# breakout.net
KiCad netlist of a schematic drawn in EAGLE
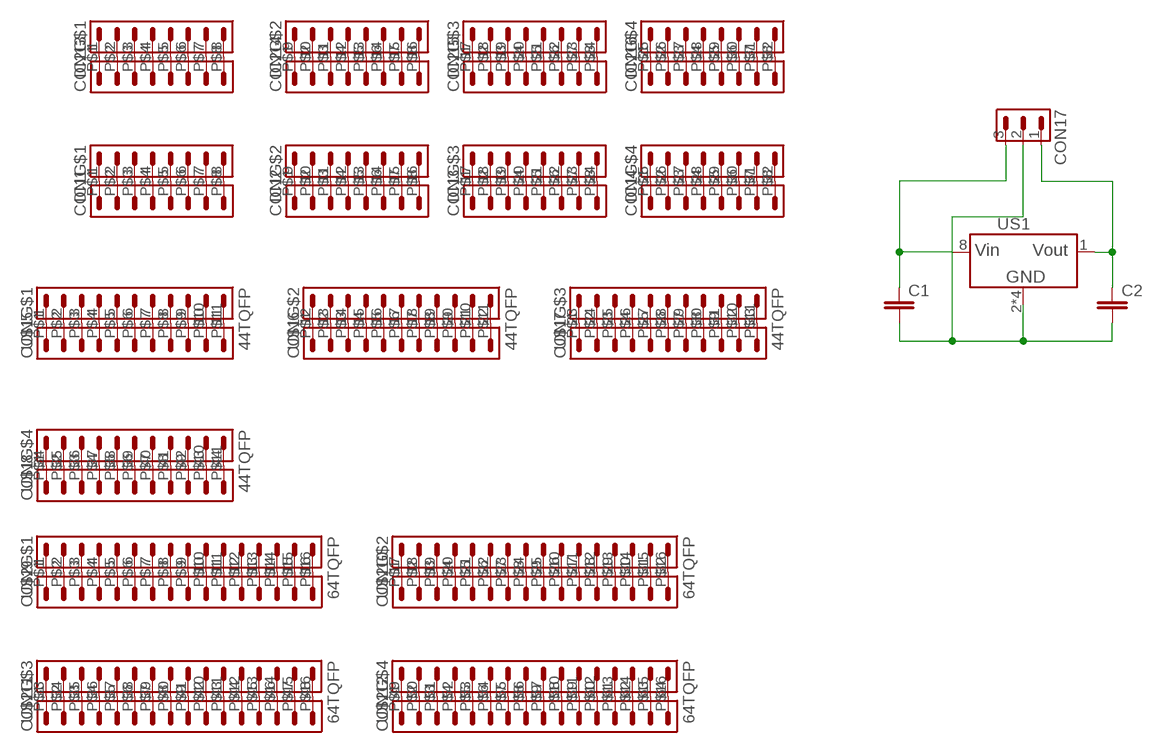
[diagram p0: schematic, sheet 1]

(export (version "E")
  (design (tool "Eeschema 10.0.6"))
  (components
    (comp (ref "C1")
      (value "C0603")
      (footprint "eagle-import:0603")
      (libsource (lib "eagle-import") (part "C0603"))
    )
    (comp (ref "C2")
      (value "C0603")
      (footprint "eagle-import:0603")
      (libsource (lib "eagle-import") (part "C0603"))
    )
    (comp (ref "CON1")
      (value "PIN8X1_SM50")
      (footprint "eagle-import:PIN8X1_SM50")
      (libsource (lib "eagle-import") (part "PIN8X1_SM50"))
    )
    (comp (ref "CON2")
      (value "PIN8X1_SM50")
      (footprint "eagle-import:PIN8X1_SM50")
      (libsource (lib "eagle-import") (part "PIN8X1_SM50"))
    )
    (comp (ref "CON3")
      (value "PIN8X1_SM50")
      (footprint "eagle-import:PIN8X1_SM50")
      (libsource (lib "eagle-import") (part "PIN8X1_SM50"))
    )
    (comp (ref "CON4")
      (value "PIN8X1_SM50")
      (footprint "eagle-import:PIN8X1_SM50")
      (libsource (lib "eagle-import") (part "PIN8X1_SM50"))
    )
    (comp (ref "CON5")
      (value "PIN11X1_SM50")
      (footprint "eagle-import:PIN11X1_SM50")
      (libsource (lib "eagle-import") (part "PIN11X1_SM50"))
    )
    (comp (ref "CON6")
      (value "PIN11X1_SM50")
      (footprint "eagle-import:PIN11X1_SM50")
      (libsource (lib "eagle-import") (part "PIN11X1_SM50"))
    )
    (comp (ref "CON7")
      (value "PIN11X1_SM50")
      (footprint "eagle-import:PIN11X1_SM50")
      (libsource (lib "eagle-import") (part "PIN11X1_SM50"))
    )
    (comp (ref "CON8")
      (value "PIN11X1_SM50")
      (footprint "eagle-import:PIN11X1_SM50")
      (libsource (lib "eagle-import") (part "PIN11X1_SM50"))
    )
    (comp (ref "CON9")
      (value "PIN16X1_SM50")
      (footprint "eagle-import:PIN16X1_SM50")
      (libsource (lib "eagle-import") (part "PIN16X1_SM50"))
    )
    (comp (ref "CON10")
      (value "PIN16X1_SM50")
      (footprint "eagle-import:PIN16X1_SM50")
      (libsource (lib "eagle-import") (part "PIN16X1_SM50"))
    )
    (comp (ref "CON11")
      (value "PIN16X1_SM50")
      (footprint "eagle-import:PIN16X1_SM50")
      (libsource (lib "eagle-import") (part "PIN16X1_SM50"))
    )
    (comp (ref "CON12")
      (value "PIN16X1_SM50")
      (footprint "eagle-import:PIN16X1_SM50")
      (libsource (lib "eagle-import") (part "PIN16X1_SM50"))
    )
    (comp (ref "CON13")
      (value "PIN8X1_SM50")
      (footprint "eagle-import:PIN8X1_SM50")
      (libsource (lib "eagle-import") (part "PIN8X1_SM50"))
    )
    (comp (ref "CON14")
      (value "PIN8X1_SM50")
      (footprint "eagle-import:PIN8X1_SM50")
      (libsource (lib "eagle-import") (part "PIN8X1_SM50"))
    )
    (comp (ref "CON15")
      (value "PIN8X1_SM50")
      (footprint "eagle-import:PIN8X1_SM50")
      (libsource (lib "eagle-import") (part "PIN8X1_SM50"))
    )
    (comp (ref "CON16")
      (value "PIN8X1_SM50")
      (footprint "eagle-import:PIN8X1_SM50")
      (libsource (lib "eagle-import") (part "PIN8X1_SM50"))
    )
    (comp (ref "CON17")
      (value "PIN3X1")
      (footprint "eagle-import:PIN3X1")
      (libsource (lib "eagle-import") (part "PIN3X1"))
    )
    (comp (ref "IC1")
      (value "32TQFP")
      (footprint "eagle-import:TQFP32")
      (libsource (lib "eagle-import") (part "32TQFP"))
    )
    (comp (ref "IC2")
      (value "32MLF")
      (footprint "eagle-import:MLF32-TH")
      (libsource (lib "eagle-import") (part "32MLF"))
    )
    (comp (ref "U$1")
      (value "44TQFP")
      (footprint "eagle-import:TQFP44")
      (libsource (lib "eagle-import") (part "44TQFP"))
    )
    (comp (ref "U$2")
      (value "64TQFP")
      (footprint "eagle-import:TQFP64")
      (libsource (lib "eagle-import") (part "64TQFP"))
    )
    (comp (ref "US1")
      (value "VREG+L-SO8")
      (footprint "eagle-import:SO08")
      (libsource (lib "eagle-import") (part "VREG+L-SO8"))
    )
  )
  (nets
    (net (code "1") (name "Net-(C1-Pad2)") (class "Default")
      (node (ref "C1") (pin "2") (pinfunction "2_2") (pintype "passive"))
      (node (ref "C2") (pin "2") (pinfunction "2_2") (pintype "passive"))
      (node (ref "CON17") (pin "2") (pinfunction "2_2") (pintype "passive"))
      (node (ref "US1") (pin "2") (pinfunction "GND_2") (pintype "passive"))
      (node (ref "US1") (pin "3") (pinfunction "GND_3") (pintype "passive"))
      (node (ref "US1") (pin "6") (pinfunction "GND_6") (pintype "passive"))
      (node (ref "US1") (pin "7") (pinfunction "GND_7") (pintype "passive"))
    )
    (net (code "2") (name "Net-(CON1-1)") (class "Default")
      (node (ref "CON1") (pin "P$1") (pinfunction "1_P$1") (pintype "passive"))
      (node (ref "IC1") (pin "1") (pinfunction "1_1") (pintype "passive"))
    )
    (net (code "3") (name "Net-(CON1-2)") (class "Default")
      (node (ref "CON1") (pin "P$2") (pinfunction "2_P$2") (pintype "passive"))
      (node (ref "IC1") (pin "2") (pinfunction "2_2") (pintype "passive"))
    )
    (net (code "4") (name "Net-(CON1-3)") (class "Default")
      (node (ref "CON1") (pin "P$3") (pinfunction "3_P$3") (pintype "passive"))
      (node (ref "IC1") (pin "3") (pinfunction "3_3") (pintype "passive"))
    )
    (net (code "5") (name "Net-(CON1-4)") (class "Default")
      (node (ref "CON1") (pin "P$4") (pinfunction "4_P$4") (pintype "passive"))
      (node (ref "IC1") (pin "4") (pinfunction "4_4") (pintype "passive"))
    )
    (net (code "6") (name "Net-(CON1-5)") (class "Default")
      (node (ref "CON1") (pin "P$5") (pinfunction "5_P$5") (pintype "passive"))
      (node (ref "IC1") (pin "5") (pinfunction "5_5") (pintype "passive"))
    )
    (net (code "7") (name "Net-(CON1-6)") (class "Default")
      (node (ref "CON1") (pin "P$6") (pinfunction "6_P$6") (pintype "passive"))
      (node (ref "IC1") (pin "6") (pinfunction "6_6") (pintype "passive"))
    )
    (net (code "8") (name "Net-(CON1-7)") (class "Default")
      (node (ref "CON1") (pin "P$7") (pinfunction "7_P$7") (pintype "passive"))
      (node (ref "IC1") (pin "7") (pinfunction "7_7") (pintype "passive"))
    )
    (net (code "9") (name "Net-(CON1-8)") (class "Default")
      (node (ref "CON1") (pin "P$8") (pinfunction "8_P$8") (pintype "passive"))
      (node (ref "IC1") (pin "8") (pinfunction "8_8") (pintype "passive"))
    )
    (net (code "10") (name "Net-(CON2-1)") (class "Default")
      (node (ref "CON2") (pin "P$1") (pinfunction "1_P$1") (pintype "passive"))
      (node (ref "IC1") (pin "9") (pinfunction "1_9") (pintype "passive"))
    )
    (net (code "11") (name "Net-(CON2-2)") (class "Default")
      (node (ref "CON2") (pin "P$2") (pinfunction "2_P$2") (pintype "passive"))
      (node (ref "IC1") (pin "10") (pinfunction "2_10") (pintype "passive"))
    )
    (net (code "12") (name "Net-(CON2-3)") (class "Default")
      (node (ref "CON2") (pin "P$3") (pinfunction "3_P$3") (pintype "passive"))
      (node (ref "IC1") (pin "11") (pinfunction "3_11") (pintype "passive"))
    )
    (net (code "13") (name "Net-(CON2-4)") (class "Default")
      (node (ref "CON2") (pin "P$4") (pinfunction "4_P$4") (pintype "passive"))
      (node (ref "IC1") (pin "12") (pinfunction "4_12") (pintype "passive"))
    )
    (net (code "14") (name "Net-(CON2-5)") (class "Default")
      (node (ref "CON2") (pin "P$5") (pinfunction "5_P$5") (pintype "passive"))
      (node (ref "IC1") (pin "13") (pinfunction "5_13") (pintype "passive"))
    )
    (net (code "15") (name "Net-(CON2-6)") (class "Default")
      (node (ref "CON2") (pin "P$6") (pinfunction "6_P$6") (pintype "passive"))
      (node (ref "IC1") (pin "14") (pinfunction "6_14") (pintype "passive"))
    )
    (net (code "16") (name "Net-(CON2-7)") (class "Default")
      (node (ref "CON2") (pin "P$7") (pinfunction "7_P$7") (pintype "passive"))
      (node (ref "IC1") (pin "15") (pinfunction "7_15") (pintype "passive"))
    )
    (net (code "17") (name "Net-(CON2-8)") (class "Default")
      (node (ref "CON2") (pin "P$8") (pinfunction "8_P$8") (pintype "passive"))
      (node (ref "IC1") (pin "16") (pinfunction "8_16") (pintype "passive"))
    )
    (net (code "18") (name "Net-(CON3-1)") (class "Default")
      (node (ref "CON3") (pin "P$1") (pinfunction "1_P$1") (pintype "passive"))
      (node (ref "IC1") (pin "17") (pinfunction "1_17") (pintype "passive"))
    )
    (net (code "19") (name "Net-(CON3-2)") (class "Default")
      (node (ref "CON3") (pin "P$2") (pinfunction "2_P$2") (pintype "passive"))
      (node (ref "IC1") (pin "18") (pinfunction "2_18") (pintype "passive"))
    )
    (net (code "20") (name "Net-(CON3-3)") (class "Default")
      (node (ref "CON3") (pin "P$3") (pinfunction "3_P$3") (pintype "passive"))
      (node (ref "IC1") (pin "19") (pinfunction "3_19") (pintype "passive"))
    )
    (net (code "21") (name "Net-(CON3-4)") (class "Default")
      (node (ref "CON3") (pin "P$4") (pinfunction "4_P$4") (pintype "passive"))
      (node (ref "IC1") (pin "20") (pinfunction "4_20") (pintype "passive"))
    )
    (net (code "22") (name "Net-(CON3-5)") (class "Default")
      (node (ref "CON3") (pin "P$5") (pinfunction "5_P$5") (pintype "passive"))
      (node (ref "IC1") (pin "21") (pinfunction "5_21") (pintype "passive"))
    )
    (net (code "23") (name "Net-(CON3-6)") (class "Default")
      (node (ref "CON3") (pin "P$6") (pinfunction "6_P$6") (pintype "passive"))
      (node (ref "IC1") (pin "22") (pinfunction "6_22") (pintype "passive"))
    )
    (net (code "24") (name "Net-(CON3-7)") (class "Default")
      (node (ref "CON3") (pin "P$7") (pinfunction "7_P$7") (pintype "passive"))
      (node (ref "IC1") (pin "23") (pinfunction "7_23") (pintype "passive"))
    )
    (net (code "25") (name "Net-(CON3-8)") (class "Default")
      (node (ref "CON3") (pin "P$8") (pinfunction "8_P$8") (pintype "passive"))
      (node (ref "IC1") (pin "24") (pinfunction "8_24") (pintype "passive"))
    )
    (net (code "26") (name "Net-(CON4-1)") (class "Default")
      (node (ref "CON4") (pin "P$1") (pinfunction "1_P$1") (pintype "passive"))
      (node (ref "IC1") (pin "25") (pinfunction "1_25") (pintype "passive"))
    )
    (net (code "27") (name "Net-(CON4-2)") (class "Default")
      (node (ref "CON4") (pin "P$2") (pinfunction "2_P$2") (pintype "passive"))
      (node (ref "IC1") (pin "26") (pinfunction "2_26") (pintype "passive"))
    )
    (net (code "28") (name "Net-(CON4-3)") (class "Default")
      (node (ref "CON4") (pin "P$3") (pinfunction "3_P$3") (pintype "passive"))
      (node (ref "IC1") (pin "27") (pinfunction "3_27") (pintype "passive"))
    )
    (net (code "29") (name "Net-(CON4-4)") (class "Default")
      (node (ref "CON4") (pin "P$4") (pinfunction "4_P$4") (pintype "passive"))
      (node (ref "IC1") (pin "28") (pinfunction "4_28") (pintype "passive"))
    )
    (net (code "30") (name "Net-(CON4-5)") (class "Default")
      (node (ref "CON4") (pin "P$5") (pinfunction "5_P$5") (pintype "passive"))
      (node (ref "IC1") (pin "29") (pinfunction "5_29") (pintype "passive"))
    )
    (net (code "31") (name "Net-(CON4-6)") (class "Default")
      (node (ref "CON4") (pin "P$6") (pinfunction "6_P$6") (pintype "passive"))
      (node (ref "IC1") (pin "30") (pinfunction "6_30") (pintype "passive"))
    )
    (net (code "32") (name "Net-(CON4-7)") (class "Default")
      (node (ref "CON4") (pin "P$7") (pinfunction "7_P$7") (pintype "passive"))
      (node (ref "IC1") (pin "31") (pinfunction "7_31") (pintype "passive"))
    )
    (net (code "33") (name "Net-(CON4-8)") (class "Default")
      (node (ref "CON4") (pin "P$8") (pinfunction "8_P$8") (pintype "passive"))
      (node (ref "IC1") (pin "32") (pinfunction "8_32") (pintype "passive"))
    )
    (net (code "34") (name "Net-(CON5-1)") (class "Default")
      (node (ref "CON5") (pin "P$1") (pinfunction "1_P$1") (pintype "passive"))
      (node (ref "U$1") (pin "1") (pinfunction "1_1") (pintype "passive"))
    )
    (net (code "35") (name "Net-(CON5-2)") (class "Default")
      (node (ref "CON5") (pin "P$2") (pinfunction "2_P$2") (pintype "passive"))
      (node (ref "U$1") (pin "2") (pinfunction "2_2") (pintype "passive"))
    )
    (net (code "36") (name "Net-(CON5-3)") (class "Default")
      (node (ref "CON5") (pin "P$3") (pinfunction "3_P$3") (pintype "passive"))
      (node (ref "U$1") (pin "3") (pinfunction "3_3") (pintype "passive"))
    )
    (net (code "37") (name "Net-(CON5-4)") (class "Default")
      (node (ref "CON5") (pin "P$4") (pinfunction "4_P$4") (pintype "passive"))
      (node (ref "U$1") (pin "4") (pinfunction "4_4") (pintype "passive"))
    )
    (net (code "38") (name "Net-(CON5-5)") (class "Default")
      (node (ref "CON5") (pin "P$5") (pinfunction "5_P$5") (pintype "passive"))
      (node (ref "U$1") (pin "5") (pinfunction "5_5") (pintype "passive"))
    )
    (net (code "39") (name "Net-(CON5-6)") (class "Default")
      (node (ref "CON5") (pin "P$6") (pinfunction "6_P$6") (pintype "passive"))
      (node (ref "U$1") (pin "6") (pinfunction "6_6") (pintype "passive"))
    )
    (net (code "40") (name "Net-(CON5-7)") (class "Default")
      (node (ref "CON5") (pin "P$7") (pinfunction "7_P$7") (pintype "passive"))
      (node (ref "U$1") (pin "7") (pinfunction "7_7") (pintype "passive"))
    )
    (net (code "41") (name "Net-(CON5-8)") (class "Default")
      (node (ref "CON5") (pin "P$8") (pinfunction "8_P$8") (pintype "passive"))
      (node (ref "U$1") (pin "8") (pinfunction "8_8") (pintype "passive"))
    )
    (net (code "42") (name "Net-(CON5-9)") (class "Default")
      (node (ref "CON5") (pin "P$9") (pinfunction "9_P$9") (pintype "passive"))
      (node (ref "U$1") (pin "9") (pinfunction "9_9") (pintype "passive"))
    )
    (net (code "43") (name "Net-(CON5-10)") (class "Default")
      (node (ref "CON5") (pin "P$10") (pinfunction "10_P$10") (pintype "passive"))
      (node (ref "U$1") (pin "10") (pinfunction "10_10") (pintype "passive"))
    )
    (net (code "44") (name "Net-(CON5-11)") (class "Default")
      (node (ref "CON5") (pin "P$11") (pinfunction "11_P$11") (pintype "passive"))
      (node (ref "U$1") (pin "11") (pinfunction "11_11") (pintype "passive"))
    )
    (net (code "45") (name "Net-(CON6-1)") (class "Default")
      (node (ref "CON6") (pin "P$1") (pinfunction "1_P$1") (pintype "passive"))
      (node (ref "U$1") (pin "12") (pinfunction "1_12") (pintype "passive"))
    )
    (net (code "46") (name "Net-(CON6-2)") (class "Default")
      (node (ref "CON6") (pin "P$2") (pinfunction "2_P$2") (pintype "passive"))
      (node (ref "U$1") (pin "13") (pinfunction "2_13") (pintype "passive"))
    )
    (net (code "47") (name "Net-(CON6-3)") (class "Default")
      (node (ref "CON6") (pin "P$3") (pinfunction "3_P$3") (pintype "passive"))
      (node (ref "U$1") (pin "14") (pinfunction "3_14") (pintype "passive"))
    )
    (net (code "48") (name "Net-(CON6-4)") (class "Default")
      (node (ref "CON6") (pin "P$4") (pinfunction "4_P$4") (pintype "passive"))
      (node (ref "U$1") (pin "15") (pinfunction "4_15") (pintype "passive"))
    )
    (net (code "49") (name "Net-(CON6-5)") (class "Default")
      (node (ref "CON6") (pin "P$5") (pinfunction "5_P$5") (pintype "passive"))
      (node (ref "U$1") (pin "16") (pinfunction "5_16") (pintype "passive"))
    )
    (net (code "50") (name "Net-(CON6-6)") (class "Default")
      (node (ref "CON6") (pin "P$6") (pinfunction "6_P$6") (pintype "passive"))
      (node (ref "U$1") (pin "17") (pinfunction "6_17") (pintype "passive"))
    )
    (net (code "51") (name "Net-(CON6-7)") (class "Default")
      (node (ref "CON6") (pin "P$7") (pinfunction "7_P$7") (pintype "passive"))
      (node (ref "U$1") (pin "18") (pinfunction "7_18") (pintype "passive"))
    )
    (net (code "52") (name "Net-(CON6-8)") (class "Default")
      (node (ref "CON6") (pin "P$8") (pinfunction "8_P$8") (pintype "passive"))
      (node (ref "U$1") (pin "19") (pinfunction "8_19") (pintype "passive"))
    )
    (net (code "53") (name "Net-(CON6-9)") (class "Default")
      (node (ref "CON6") (pin "P$9") (pinfunction "9_P$9") (pintype "passive"))
      (node (ref "U$1") (pin "20") (pinfunction "9_20") (pintype "passive"))
    )
    (net (code "54") (name "Net-(CON6-10)") (class "Default")
      (node (ref "CON6") (pin "P$10") (pinfunction "10_P$10") (pintype "passive"))
      (node (ref "U$1") (pin "21") (pinfunction "10_21") (pintype "passive"))
    )
    (net (code "55") (name "Net-(CON6-11)") (class "Default")
      (node (ref "CON6") (pin "P$11") (pinfunction "11_P$11") (pintype "passive"))
      (node (ref "U$1") (pin "22") (pinfunction "11_22") (pintype "passive"))
    )
    (net (code "56") (name "Net-(CON7-1)") (class "Default")
      (node (ref "CON7") (pin "P$1") (pinfunction "1_P$1") (pintype "passive"))
      (node (ref "U$1") (pin "23") (pinfunction "1_23") (pintype "passive"))
    )
    (net (code "57") (name "Net-(CON7-2)") (class "Default")
      (node (ref "CON7") (pin "P$2") (pinfunction "2_P$2") (pintype "passive"))
      (node (ref "U$1") (pin "24") (pinfunction "2_24") (pintype "passive"))
    )
    (net (code "58") (name "Net-(CON7-3)") (class "Default")
      (node (ref "CON7") (pin "P$3") (pinfunction "3_P$3") (pintype "passive"))
      (node (ref "U$1") (pin "25") (pinfunction "3_25") (pintype "passive"))
    )
    (net (code "59") (name "Net-(CON7-4)") (class "Default")
      (node (ref "CON7") (pin "P$4") (pinfunction "4_P$4") (pintype "passive"))
      (node (ref "U$1") (pin "26") (pinfunction "4_26") (pintype "passive"))
    )
    (net (code "60") (name "Net-(CON7-5)") (class "Default")
      (node (ref "CON7") (pin "P$5") (pinfunction "5_P$5") (pintype "passive"))
      (node (ref "U$1") (pin "27") (pinfunction "5_27") (pintype "passive"))
    )
    (net (code "61") (name "Net-(CON7-6)") (class "Default")
      (node (ref "CON7") (pin "P$6") (pinfunction "6_P$6") (pintype "passive"))
      (node (ref "U$1") (pin "28") (pinfunction "6_28") (pintype "passive"))
    )
    (net (code "62") (name "Net-(CON7-7)") (class "Default")
      (node (ref "CON7") (pin "P$7") (pinfunction "7_P$7") (pintype "passive"))
      (node (ref "U$1") (pin "29") (pinfunction "7_29") (pintype "passive"))
    )
    (net (code "63") (name "Net-(CON7-8)") (class "Default")
      (node (ref "CON7") (pin "P$8") (pinfunction "8_P$8") (pintype "passive"))
      (node (ref "U$1") (pin "30") (pinfunction "8_30") (pintype "passive"))
    )
    (net (code "64") (name "Net-(CON7-9)") (class "Default")
      (node (ref "CON7") (pin "P$9") (pinfunction "9_P$9") (pintype "passive"))
      (node (ref "U$1") (pin "31") (pinfunction "9_31") (pintype "passive"))
    )
    (net (code "65") (name "Net-(CON7-10)") (class "Default")
      (node (ref "CON7") (pin "P$10") (pinfunction "10_P$10") (pintype "passive"))
      (node (ref "U$1") (pin "32") (pinfunction "10_32") (pintype "passive"))
    )
    (net (code "66") (name "Net-(CON7-11)") (class "Default")
      (node (ref "CON7") (pin "P$11") (pinfunction "11_P$11") (pintype "passive"))
      (node (ref "U$1") (pin "33") (pinfunction "11_33") (pintype "passive"))
    )
    (net (code "67") (name "Net-(CON8-1)") (class "Default")
      (node (ref "CON8") (pin "P$1") (pinfunction "1_P$1") (pintype "passive"))
      (node (ref "U$1") (pin "34") (pinfunction "1_34") (pintype "passive"))
    )
    (net (code "68") (name "Net-(CON8-2)") (class "Default")
      (node (ref "CON8") (pin "P$2") (pinfunction "2_P$2") (pintype "passive"))
      (node (ref "U$1") (pin "35") (pinfunction "2_35") (pintype "passive"))
    )
    (net (code "69") (name "Net-(CON8-3)") (class "Default")
      (node (ref "CON8") (pin "P$3") (pinfunction "3_P$3") (pintype "passive"))
      (node (ref "U$1") (pin "36") (pinfunction "3_36") (pintype "passive"))
    )
    (net (code "70") (name "Net-(CON8-4)") (class "Default")
      (node (ref "CON8") (pin "P$4") (pinfunction "4_P$4") (pintype "passive"))
      (node (ref "U$1") (pin "37") (pinfunction "4_37") (pintype "passive"))
    )
    (net (code "71") (name "Net-(CON8-5)") (class "Default")
      (node (ref "CON8") (pin "P$5") (pinfunction "5_P$5") (pintype "passive"))
      (node (ref "U$1") (pin "38") (pinfunction "5_38") (pintype "passive"))
    )
    (net (code "72") (name "Net-(CON8-6)") (class "Default")
      (node (ref "CON8") (pin "P$6") (pinfunction "6_P$6") (pintype "passive"))
      (node (ref "U$1") (pin "39") (pinfunction "6_39") (pintype "passive"))
    )
    (net (code "73") (name "Net-(CON8-7)") (class "Default")
      (node (ref "CON8") (pin "P$7") (pinfunction "7_P$7") (pintype "passive"))
      (node (ref "U$1") (pin "40") (pinfunction "7_40") (pintype "passive"))
    )
    (net (code "74") (name "Net-(CON8-8)") (class "Default")
      (node (ref "CON8") (pin "P$8") (pinfunction "8_P$8") (pintype "passive"))
      (node (ref "U$1") (pin "41") (pinfunction "8_41") (pintype "passive"))
    )
    (net (code "75") (name "Net-(CON8-9)") (class "Default")
      (node (ref "CON8") (pin "P$9") (pinfunction "9_P$9") (pintype "passive"))
      (node (ref "U$1") (pin "42") (pinfunction "9_42") (pintype "passive"))
    )
    (net (code "76") (name "Net-(CON8-10)") (class "Default")
      (node (ref "CON8") (pin "P$10") (pinfunction "10_P$10") (pintype "passive"))
      (node (ref "U$1") (pin "43") (pinfunction "10_43") (pintype "passive"))
    )
    (net (code "77") (name "Net-(CON8-11)") (class "Default")
      (node (ref "CON8") (pin "P$11") (pinfunction "11_P$11") (pintype "passive"))
      (node (ref "U$1") (pin "44") (pinfunction "11_44") (pintype "passive"))
    )
    (net (code "78") (name "Net-(CON9-1)") (class "Default")
      (node (ref "CON9") (pin "P$1") (pinfunction "1_P$1") (pintype "passive"))
      (node (ref "U$2") (pin "1") (pinfunction "1_1") (pintype "passive"))
    )
    (net (code "79") (name "Net-(CON9-2)") (class "Default")
      (node (ref "CON9") (pin "P$2") (pinfunction "2_P$2") (pintype "passive"))
      (node (ref "U$2") (pin "2") (pinfunction "2_2") (pintype "passive"))
    )
    (net (code "80") (name "Net-(CON9-3)") (class "Default")
      (node (ref "CON9") (pin "P$3") (pinfunction "3_P$3") (pintype "passive"))
      (node (ref "U$2") (pin "3") (pinfunction "3_3") (pintype "passive"))
    )
    (net (code "81") (name "Net-(CON9-4)") (class "Default")
      (node (ref "CON9") (pin "P$4") (pinfunction "4_P$4") (pintype "passive"))
      (node (ref "U$2") (pin "4") (pinfunction "4_4") (pintype "passive"))
    )
    (net (code "82") (name "Net-(CON9-5)") (class "Default")
      (node (ref "CON9") (pin "P$5") (pinfunction "5_P$5") (pintype "passive"))
      (node (ref "U$2") (pin "5") (pinfunction "5_5") (pintype "passive"))
    )
    (net (code "83") (name "Net-(CON9-6)") (class "Default")
      (node (ref "CON9") (pin "P$6") (pinfunction "6_P$6") (pintype "passive"))
      (node (ref "U$2") (pin "6") (pinfunction "6_6") (pintype "passive"))
    )
    (net (code "84") (name "Net-(CON9-7)") (class "Default")
      (node (ref "CON9") (pin "P$7") (pinfunction "7_P$7") (pintype "passive"))
      (node (ref "U$2") (pin "7") (pinfunction "7_7") (pintype "passive"))
    )
    (net (code "85") (name "Net-(CON9-8)") (class "Default")
      (node (ref "CON9") (pin "P$8") (pinfunction "8_P$8") (pintype "passive"))
      (node (ref "U$2") (pin "8") (pinfunction "8_8") (pintype "passive"))
    )
    (net (code "86") (name "Net-(CON9-9)") (class "Default")
      (node (ref "CON9") (pin "P$9") (pinfunction "9_P$9") (pintype "passive"))
      (node (ref "U$2") (pin "9") (pinfunction "9_9") (pintype "passive"))
    )
    (net (code "87") (name "Net-(CON9-10)") (class "Default")
      (node (ref "CON9") (pin "P$10") (pinfunction "10_P$10") (pintype "passive"))
      (node (ref "U$2") (pin "10") (pinfunction "10_10") (pintype "passive"))
    )
    (net (code "88") (name "Net-(CON9-11)") (class "Default")
      (node (ref "CON9") (pin "P$11") (pinfunction "11_P$11") (pintype "passive"))
      (node (ref "U$2") (pin "11") (pinfunction "11_11") (pintype "passive"))
    )
    (net (code "89") (name "Net-(CON9-12)") (class "Default")
      (node (ref "CON9") (pin "P$12") (pinfunction "12_P$12") (pintype "passive"))
      (node (ref "U$2") (pin "12") (pinfunction "12_12") (pintype "passive"))
    )
    (net (code "90") (name "Net-(CON9-13)") (class "Default")
      (node (ref "CON9") (pin "P$13") (pinfunction "13_P$13") (pintype "passive"))
      (node (ref "U$2") (pin "13") (pinfunction "13_13") (pintype "passive"))
    )
    (net (code "91") (name "Net-(CON9-14)") (class "Default")
      (node (ref "CON9") (pin "P$14") (pinfunction "14_P$14") (pintype "passive"))
      (node (ref "U$2") (pin "14") (pinfunction "14_14") (pintype "passive"))
    )
    (net (code "92") (name "Net-(CON9-15)") (class "Default")
      (node (ref "CON9") (pin "P$15") (pinfunction "15_P$15") (pintype "passive"))
      (node (ref "U$2") (pin "15") (pinfunction "15_15") (pintype "passive"))
    )
    (net (code "93") (name "Net-(CON9-16)") (class "Default")
      (node (ref "CON9") (pin "P$16") (pinfunction "16_P$16") (pintype "passive"))
      (node (ref "U$2") (pin "16") (pinfunction "16_16") (pintype "passive"))
    )
    (net (code "94") (name "Net-(CON10-1)") (class "Default")
      (node (ref "CON10") (pin "P$1") (pinfunction "1_P$1") (pintype "passive"))
      (node (ref "U$2") (pin "17") (pinfunction "1_17") (pintype "passive"))
    )
    (net (code "95") (name "Net-(CON10-2)") (class "Default")
      (node (ref "CON10") (pin "P$2") (pinfunction "2_P$2") (pintype "passive"))
      (node (ref "U$2") (pin "18") (pinfunction "2_18") (pintype "passive"))
    )
    (net (code "96") (name "Net-(CON10-3)") (class "Default")
      (node (ref "CON10") (pin "P$3") (pinfunction "3_P$3") (pintype "passive"))
      (node (ref "U$2") (pin "19") (pinfunction "3_19") (pintype "passive"))
    )
    (net (code "97") (name "Net-(CON10-4)") (class "Default")
      (node (ref "CON10") (pin "P$4") (pinfunction "4_P$4") (pintype "passive"))
      (node (ref "U$2") (pin "20") (pinfunction "4_20") (pintype "passive"))
    )
    (net (code "98") (name "Net-(CON10-5)") (class "Default")
      (node (ref "CON10") (pin "P$5") (pinfunction "5_P$5") (pintype "passive"))
      (node (ref "U$2") (pin "21") (pinfunction "5_21") (pintype "passive"))
    )
    (net (code "99") (name "Net-(CON10-6)") (class "Default")
      (node (ref "CON10") (pin "P$6") (pinfunction "6_P$6") (pintype "passive"))
      (node (ref "U$2") (pin "22") (pinfunction "6_22") (pintype "passive"))
    )
    (net (code "100") (name "Net-(CON10-7)") (class "Default")
      (node (ref "CON10") (pin "P$7") (pinfunction "7_P$7") (pintype "passive"))
      (node (ref "U$2") (pin "23") (pinfunction "7_23") (pintype "passive"))
    )
    (net (code "101") (name "Net-(CON10-8)") (class "Default")
      (node (ref "CON10") (pin "P$8") (pinfunction "8_P$8") (pintype "passive"))
      (node (ref "U$2") (pin "24") (pinfunction "8_24") (pintype "passive"))
    )
    (net (code "102") (name "Net-(CON10-9)") (class "Default")
      (node (ref "CON10") (pin "P$9") (pinfunction "9_P$9") (pintype "passive"))
      (node (ref "U$2") (pin "25") (pinfunction "9_25") (pintype "passive"))
    )
    (net (code "103") (name "Net-(CON10-10)") (class "Default")
      (node (ref "CON10") (pin "P$10") (pinfunction "10_P$10") (pintype "passive"))
      (node (ref "U$2") (pin "26") (pinfunction "10_26") (pintype "passive"))
    )
    (net (code "104") (name "Net-(CON10-11)") (class "Default")
      (node (ref "CON10") (pin "P$11") (pinfunction "11_P$11") (pintype "passive"))
      (node (ref "U$2") (pin "27") (pinfunction "11_27") (pintype "passive"))
    )
    (net (code "105") (name "Net-(CON10-12)") (class "Default")
      (node (ref "CON10") (pin "P$12") (pinfunction "12_P$12") (pintype "passive"))
      (node (ref "U$2") (pin "28") (pinfunction "12_28") (pintype "passive"))
    )
    (net (code "106") (name "Net-(CON10-13)") (class "Default")
      (node (ref "CON10") (pin "P$13") (pinfunction "13_P$13") (pintype "passive"))
      (node (ref "U$2") (pin "29") (pinfunction "13_29") (pintype "passive"))
    )
    (net (code "107") (name "Net-(CON10-14)") (class "Default")
      (node (ref "CON10") (pin "P$14") (pinfunction "14_P$14") (pintype "passive"))
      (node (ref "U$2") (pin "30") (pinfunction "14_30") (pintype "passive"))
    )
    (net (code "108") (name "Net-(CON10-15)") (class "Default")
      (node (ref "CON10") (pin "P$15") (pinfunction "15_P$15") (pintype "passive"))
      (node (ref "U$2") (pin "31") (pinfunction "15_31") (pintype "passive"))
    )
    (net (code "109") (name "Net-(CON10-16)") (class "Default")
      (node (ref "CON10") (pin "P$16") (pinfunction "16_P$16") (pintype "passive"))
      (node (ref "U$2") (pin "32") (pinfunction "16_32") (pintype "passive"))
    )
    (net (code "110") (name "Net-(CON11-1)") (class "Default")
      (node (ref "CON11") (pin "P$1") (pinfunction "1_P$1") (pintype "passive"))
      (node (ref "U$2") (pin "33") (pinfunction "1_33") (pintype "passive"))
    )
    (net (code "111") (name "Net-(CON11-2)") (class "Default")
      (node (ref "CON11") (pin "P$2") (pinfunction "2_P$2") (pintype "passive"))
      (node (ref "U$2") (pin "34") (pinfunction "2_34") (pintype "passive"))
    )
    (net (code "112") (name "Net-(CON11-3)") (class "Default")
      (node (ref "CON11") (pin "P$3") (pinfunction "3_P$3") (pintype "passive"))
      (node (ref "U$2") (pin "35") (pinfunction "3_35") (pintype "passive"))
    )
    (net (code "113") (name "Net-(CON11-4)") (class "Default")
      (node (ref "CON11") (pin "P$4") (pinfunction "4_P$4") (pintype "passive"))
      (node (ref "U$2") (pin "36") (pinfunction "4_36") (pintype "passive"))
    )
    (net (code "114") (name "Net-(CON11-5)") (class "Default")
      (node (ref "CON11") (pin "P$5") (pinfunction "5_P$5") (pintype "passive"))
      (node (ref "U$2") (pin "37") (pinfunction "5_37") (pintype "passive"))
    )
    (net (code "115") (name "Net-(CON11-6)") (class "Default")
      (node (ref "CON11") (pin "P$6") (pinfunction "6_P$6") (pintype "passive"))
      (node (ref "U$2") (pin "38") (pinfunction "6_38") (pintype "passive"))
    )
    (net (code "116") (name "Net-(CON11-7)") (class "Default")
      (node (ref "CON11") (pin "P$7") (pinfunction "7_P$7") (pintype "passive"))
      (node (ref "U$2") (pin "39") (pinfunction "7_39") (pintype "passive"))
    )
    (net (code "117") (name "Net-(CON11-8)") (class "Default")
      (node (ref "CON11") (pin "P$8") (pinfunction "8_P$8") (pintype "passive"))
      (node (ref "U$2") (pin "40") (pinfunction "8_40") (pintype "passive"))
    )
    (net (code "118") (name "Net-(CON11-9)") (class "Default")
      (node (ref "CON11") (pin "P$9") (pinfunction "9_P$9") (pintype "passive"))
      (node (ref "U$2") (pin "41") (pinfunction "9_41") (pintype "passive"))
    )
    (net (code "119") (name "Net-(CON11-10)") (class "Default")
      (node (ref "CON11") (pin "P$10") (pinfunction "10_P$10") (pintype "passive"))
      (node (ref "U$2") (pin "42") (pinfunction "10_42") (pintype "passive"))
    )
    (net (code "120") (name "Net-(CON11-11)") (class "Default")
      (node (ref "CON11") (pin "P$11") (pinfunction "11_P$11") (pintype "passive"))
      (node (ref "U$2") (pin "43") (pinfunction "11_43") (pintype "passive"))
    )
    (net (code "121") (name "Net-(CON11-12)") (class "Default")
      (node (ref "CON11") (pin "P$12") (pinfunction "12_P$12") (pintype "passive"))
      (node (ref "U$2") (pin "44") (pinfunction "12_44") (pintype "passive"))
    )
    (net (code "122") (name "Net-(CON11-13)") (class "Default")
      (node (ref "CON11") (pin "P$13") (pinfunction "13_P$13") (pintype "passive"))
      (node (ref "U$2") (pin "45") (pinfunction "13_45") (pintype "passive"))
    )
    (net (code "123") (name "Net-(CON11-14)") (class "Default")
      (node (ref "CON11") (pin "P$14") (pinfunction "14_P$14") (pintype "passive"))
      (node (ref "U$2") (pin "46") (pinfunction "14_46") (pintype "passive"))
    )
    (net (code "124") (name "Net-(CON11-15)") (class "Default")
      (node (ref "CON11") (pin "P$15") (pinfunction "15_P$15") (pintype "passive"))
      (node (ref "U$2") (pin "47") (pinfunction "15_47") (pintype "passive"))
    )
    (net (code "125") (name "Net-(CON11-16)") (class "Default")
      (node (ref "CON11") (pin "P$16") (pinfunction "16_P$16") (pintype "passive"))
      (node (ref "U$2") (pin "48") (pinfunction "16_48") (pintype "passive"))
    )
    (net (code "126") (name "Net-(CON12-1)") (class "Default")
      (node (ref "CON12") (pin "P$1") (pinfunction "1_P$1") (pintype "passive"))
      (node (ref "U$2") (pin "49") (pinfunction "1_49") (pintype "passive"))
    )
    (net (code "127") (name "Net-(CON12-2)") (class "Default")
      (node (ref "CON12") (pin "P$2") (pinfunction "2_P$2") (pintype "passive"))
      (node (ref "U$2") (pin "50") (pinfunction "2_50") (pintype "passive"))
    )
    (net (code "128") (name "Net-(CON12-3)") (class "Default")
      (node (ref "CON12") (pin "P$3") (pinfunction "3_P$3") (pintype "passive"))
      (node (ref "U$2") (pin "51") (pinfunction "3_51") (pintype "passive"))
    )
    (net (code "129") (name "Net-(CON12-4)") (class "Default")
      (node (ref "CON12") (pin "P$4") (pinfunction "4_P$4") (pintype "passive"))
      (node (ref "U$2") (pin "52") (pinfunction "4_52") (pintype "passive"))
    )
    (net (code "130") (name "Net-(CON12-5)") (class "Default")
      (node (ref "CON12") (pin "P$5") (pinfunction "5_P$5") (pintype "passive"))
      (node (ref "U$2") (pin "53") (pinfunction "5_53") (pintype "passive"))
    )
    (net (code "131") (name "Net-(CON12-6)") (class "Default")
      (node (ref "CON12") (pin "P$6") (pinfunction "6_P$6") (pintype "passive"))
      (node (ref "U$2") (pin "54") (pinfunction "6_54") (pintype "passive"))
    )
    (net (code "132") (name "Net-(CON12-7)") (class "Default")
      (node (ref "CON12") (pin "P$7") (pinfunction "7_P$7") (pintype "passive"))
      (node (ref "U$2") (pin "55") (pinfunction "7_55") (pintype "passive"))
    )
    (net (code "133") (name "Net-(CON12-8)") (class "Default")
      (node (ref "CON12") (pin "P$8") (pinfunction "8_P$8") (pintype "passive"))
      (node (ref "U$2") (pin "56") (pinfunction "8_56") (pintype "passive"))
    )
    (net (code "134") (name "Net-(CON12-9)") (class "Default")
      (node (ref "CON12") (pin "P$9") (pinfunction "9_P$9") (pintype "passive"))
      (node (ref "U$2") (pin "57") (pinfunction "9_57") (pintype "passive"))
    )
    (net (code "135") (name "Net-(CON12-10)") (class "Default")
      (node (ref "CON12") (pin "P$10") (pinfunction "10_P$10") (pintype "passive"))
      (node (ref "U$2") (pin "58") (pinfunction "10_58") (pintype "passive"))
    )
    (net (code "136") (name "Net-(CON12-11)") (class "Default")
      (node (ref "CON12") (pin "P$11") (pinfunction "11_P$11") (pintype "passive"))
      (node (ref "U$2") (pin "59") (pinfunction "11_59") (pintype "passive"))
    )
    (net (code "137") (name "Net-(CON12-12)") (class "Default")
      (node (ref "CON12") (pin "P$12") (pinfunction "12_P$12") (pintype "passive"))
      (node (ref "U$2") (pin "60") (pinfunction "12_60") (pintype "passive"))
    )
    (net (code "138") (name "Net-(CON12-13)") (class "Default")
      (node (ref "CON12") (pin "P$13") (pinfunction "13_P$13") (pintype "passive"))
      (node (ref "U$2") (pin "61") (pinfunction "13_61") (pintype "passive"))
    )
    (net (code "139") (name "Net-(CON12-14)") (class "Default")
      (node (ref "CON12") (pin "P$14") (pinfunction "14_P$14") (pintype "passive"))
      (node (ref "U$2") (pin "62") (pinfunction "14_62") (pintype "passive"))
    )
    (net (code "140") (name "Net-(CON12-15)") (class "Default")
      (node (ref "CON12") (pin "P$15") (pinfunction "15_P$15") (pintype "passive"))
      (node (ref "U$2") (pin "63") (pinfunction "15_63") (pintype "passive"))
    )
    (net (code "141") (name "Net-(CON12-16)") (class "Default")
      (node (ref "CON12") (pin "P$16") (pinfunction "16_P$16") (pintype "passive"))
      (node (ref "U$2") (pin "64") (pinfunction "16_64") (pintype "passive"))
    )
    (net (code "142") (name "Net-(CON13-1)") (class "Default")
      (node (ref "CON13") (pin "P$1") (pinfunction "1_P$1") (pintype "passive"))
      (node (ref "IC2") (pin "1") (pinfunction "1_1") (pintype "passive"))
    )
    (net (code "143") (name "Net-(CON13-2)") (class "Default")
      (node (ref "CON13") (pin "P$2") (pinfunction "2_P$2") (pintype "passive"))
      (node (ref "IC2") (pin "2") (pinfunction "2_2") (pintype "passive"))
    )
    (net (code "144") (name "Net-(CON13-3)") (class "Default")
      (node (ref "CON13") (pin "P$3") (pinfunction "3_P$3") (pintype "passive"))
      (node (ref "IC2") (pin "3") (pinfunction "3_3") (pintype "passive"))
    )
    (net (code "145") (name "Net-(CON13-4)") (class "Default")
      (node (ref "CON13") (pin "P$4") (pinfunction "4_P$4") (pintype "passive"))
      (node (ref "IC2") (pin "4") (pinfunction "4_4") (pintype "passive"))
    )
    (net (code "146") (name "Net-(CON13-5)") (class "Default")
      (node (ref "CON13") (pin "P$5") (pinfunction "5_P$5") (pintype "passive"))
      (node (ref "IC2") (pin "5") (pinfunction "5_5") (pintype "passive"))
    )
    (net (code "147") (name "Net-(CON13-6)") (class "Default")
      (node (ref "CON13") (pin "P$6") (pinfunction "6_P$6") (pintype "passive"))
      (node (ref "IC2") (pin "6") (pinfunction "6_6") (pintype "passive"))
    )
    (net (code "148") (name "Net-(CON13-7)") (class "Default")
      (node (ref "CON13") (pin "P$7") (pinfunction "7_P$7") (pintype "passive"))
      (node (ref "IC2") (pin "7") (pinfunction "7_7") (pintype "passive"))
    )
    (net (code "149") (name "Net-(CON13-8)") (class "Default")
      (node (ref "CON13") (pin "P$8") (pinfunction "8_P$8") (pintype "passive"))
      (node (ref "IC2") (pin "8") (pinfunction "8_8") (pintype "passive"))
    )
    (net (code "150") (name "Net-(CON14-1)") (class "Default")
      (node (ref "CON14") (pin "P$1") (pinfunction "1_P$1") (pintype "passive"))
      (node (ref "IC2") (pin "9") (pinfunction "1_9") (pintype "passive"))
    )
    (net (code "151") (name "Net-(CON14-2)") (class "Default")
      (node (ref "CON14") (pin "P$2") (pinfunction "2_P$2") (pintype "passive"))
      (node (ref "IC2") (pin "10") (pinfunction "2_10") (pintype "passive"))
    )
    (net (code "152") (name "Net-(CON14-3)") (class "Default")
      (node (ref "CON14") (pin "P$3") (pinfunction "3_P$3") (pintype "passive"))
      (node (ref "IC2") (pin "11") (pinfunction "3_11") (pintype "passive"))
    )
    (net (code "153") (name "Net-(CON14-4)") (class "Default")
      (node (ref "CON14") (pin "P$4") (pinfunction "4_P$4") (pintype "passive"))
      (node (ref "IC2") (pin "12") (pinfunction "4_12") (pintype "passive"))
    )
    (net (code "154") (name "Net-(CON14-5)") (class "Default")
      (node (ref "CON14") (pin "P$5") (pinfunction "5_P$5") (pintype "passive"))
      (node (ref "IC2") (pin "13") (pinfunction "5_13") (pintype "passive"))
    )
    (net (code "155") (name "Net-(CON14-6)") (class "Default")
      (node (ref "CON14") (pin "P$6") (pinfunction "6_P$6") (pintype "passive"))
      (node (ref "IC2") (pin "14") (pinfunction "6_14") (pintype "passive"))
    )
    (net (code "156") (name "Net-(CON14-7)") (class "Default")
      (node (ref "CON14") (pin "P$7") (pinfunction "7_P$7") (pintype "passive"))
      (node (ref "IC2") (pin "15") (pinfunction "7_15") (pintype "passive"))
    )
    (net (code "157") (name "Net-(CON14-8)") (class "Default")
      (node (ref "CON14") (pin "P$8") (pinfunction "8_P$8") (pintype "passive"))
      (node (ref "IC2") (pin "16") (pinfunction "8_16") (pintype "passive"))
    )
    (net (code "158") (name "Net-(CON15-1)") (class "Default")
      (node (ref "CON15") (pin "P$1") (pinfunction "1_P$1") (pintype "passive"))
      (node (ref "IC2") (pin "17") (pinfunction "1_17") (pintype "passive"))
    )
    (net (code "159") (name "Net-(CON15-2)") (class "Default")
      (node (ref "CON15") (pin "P$2") (pinfunction "2_P$2") (pintype "passive"))
      (node (ref "IC2") (pin "18") (pinfunction "2_18") (pintype "passive"))
    )
    (net (code "160") (name "Net-(CON15-3)") (class "Default")
      (node (ref "CON15") (pin "P$3") (pinfunction "3_P$3") (pintype "passive"))
      (node (ref "IC2") (pin "19") (pinfunction "3_19") (pintype "passive"))
    )
    (net (code "161") (name "Net-(CON15-4)") (class "Default")
      (node (ref "CON15") (pin "P$4") (pinfunction "4_P$4") (pintype "passive"))
      (node (ref "IC2") (pin "20") (pinfunction "4_20") (pintype "passive"))
    )
    (net (code "162") (name "Net-(CON15-5)") (class "Default")
      (node (ref "CON15") (pin "P$5") (pinfunction "5_P$5") (pintype "passive"))
      (node (ref "IC2") (pin "21") (pinfunction "5_21") (pintype "passive"))
    )
    (net (code "163") (name "Net-(CON15-6)") (class "Default")
      (node (ref "CON15") (pin "P$6") (pinfunction "6_P$6") (pintype "passive"))
      (node (ref "IC2") (pin "22") (pinfunction "6_22") (pintype "passive"))
    )
    (net (code "164") (name "Net-(CON15-7)") (class "Default")
      (node (ref "CON15") (pin "P$7") (pinfunction "7_P$7") (pintype "passive"))
      (node (ref "IC2") (pin "23") (pinfunction "7_23") (pintype "passive"))
    )
    (net (code "165") (name "Net-(CON15-8)") (class "Default")
      (node (ref "CON15") (pin "P$8") (pinfunction "8_P$8") (pintype "passive"))
      (node (ref "IC2") (pin "24") (pinfunction "8_24") (pintype "passive"))
    )
    (net (code "166") (name "Net-(CON16-1)") (class "Default")
      (node (ref "CON16") (pin "P$1") (pinfunction "1_P$1") (pintype "passive"))
      (node (ref "IC2") (pin "25") (pinfunction "1_25") (pintype "passive"))
    )
    (net (code "167") (name "Net-(CON16-2)") (class "Default")
      (node (ref "CON16") (pin "P$2") (pinfunction "2_P$2") (pintype "passive"))
      (node (ref "IC2") (pin "26") (pinfunction "2_26") (pintype "passive"))
    )
    (net (code "168") (name "Net-(CON16-3)") (class "Default")
      (node (ref "CON16") (pin "P$3") (pinfunction "3_P$3") (pintype "passive"))
      (node (ref "IC2") (pin "27") (pinfunction "3_27") (pintype "passive"))
    )
    (net (code "169") (name "Net-(CON16-4)") (class "Default")
      (node (ref "CON16") (pin "P$4") (pinfunction "4_P$4") (pintype "passive"))
      (node (ref "IC2") (pin "28") (pinfunction "4_28") (pintype "passive"))
    )
    (net (code "170") (name "Net-(CON16-5)") (class "Default")
      (node (ref "CON16") (pin "P$5") (pinfunction "5_P$5") (pintype "passive"))
      (node (ref "IC2") (pin "29") (pinfunction "5_29") (pintype "passive"))
    )
    (net (code "171") (name "Net-(CON16-6)") (class "Default")
      (node (ref "CON16") (pin "P$6") (pinfunction "6_P$6") (pintype "passive"))
      (node (ref "IC2") (pin "30") (pinfunction "6_30") (pintype "passive"))
    )
    (net (code "172") (name "Net-(CON16-7)") (class "Default")
      (node (ref "CON16") (pin "P$7") (pinfunction "7_P$7") (pintype "passive"))
      (node (ref "IC2") (pin "31") (pinfunction "7_31") (pintype "passive"))
    )
    (net (code "173") (name "Net-(CON16-8)") (class "Default")
      (node (ref "CON16") (pin "P$8") (pinfunction "8_P$8") (pintype "passive"))
      (node (ref "IC2") (pin "32") (pinfunction "8_32") (pintype "passive"))
    )
    (net (code "174") (name "Net-(US1-IN)") (class "Default")
      (node (ref "C1") (pin "1") (pinfunction "1_1") (pintype "passive"))
      (node (ref "CON17") (pin "3") (pinfunction "3_3") (pintype "passive"))
      (node (ref "US1") (pin "8") (pinfunction "IN_8") (pintype "input"))
    )
    (net (code "175") (name "Net-(US1-OUT)") (class "Default")
      (node (ref "C2") (pin "1") (pinfunction "1_1") (pintype "passive"))
      (node (ref "CON17") (pin "1") (pinfunction "1_1") (pintype "passive"))
      (node (ref "US1") (pin "1") (pinfunction "OUT_1") (pintype "passive"))
    )
  )
)
